# Maket.net
KiCad netlist of a schematic drawn in Altium Designer
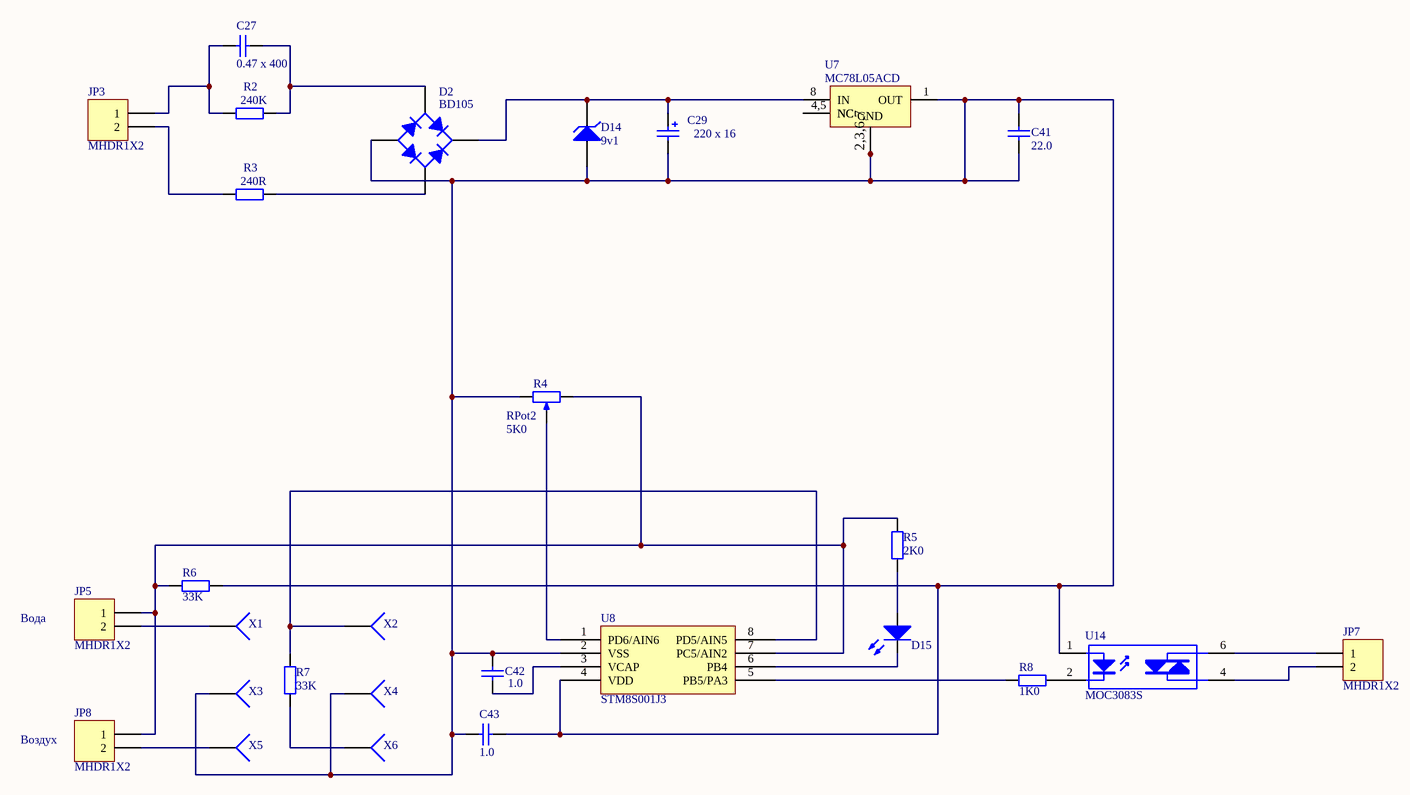
[diagram p0: Maket.SchDoc]

(export (version "E")
  (design (tool "Eeschema 10.0.6"))
  (components
    (comp (ref "C27")
      (value "0.47 x 400")
      (footprint "_1206")
      (description "Capacitor")
      (fields (field (name "MANUFACTURER") "Generic Components") (field (name "PUBLISHER") "Altium Limited"))
      (libsource (lib "Miscellaneous Devices") (part "Cap Semi"))
    )
    (comp (ref "C29")
      (value "220 x 16")
      (footprint "el3")
      (description "Polarized Capacitor (Radial)")
      (fields (field (name "MANUFACTURER") "Generic Components") (field (name "PUBLISHER") "Altium Limited"))
      (libsource (lib "PAL") (part "Cap Pol1"))
    )
    (comp (ref "C41")
      (value "22.0")
      (footprint "_1206")
      (description "Capacitor (Semiconductor SIM Model)")
      (fields (field (name "MANUFACTURER") "Generic Components") (field (name "PUBLISHER") "Altium Limited"))
      (libsource (lib "Miscellaneous Devices") (part "Cap Semi"))
    )
    (comp (ref "C42")
      (value "1.0")
      (footprint "_1206")
      (description "Capacitor")
      (fields (field (name "MANUFACTURER") "Generic Components") (field (name "PUBLISHER") "Altium Limited"))
      (libsource (lib "Miscellaneous Devices") (part "Cap Semi"))
    )
    (comp (ref "C43")
      (value "1.0")
      (footprint "_1206")
      (description "Capacitor")
      (fields (field (name "MANUFACTURER") "Generic Components") (field (name "PUBLISHER") "Altium Limited"))
      (libsource (lib "Miscellaneous Devices") (part "Cap Semi"))
    )
    (comp (ref "D2")
      (value "BD105")
      (footprint "DF01")
      (description "Full Wave Diode Bridge")
      (fields (field (name "MANUFACTURER") "Generic Components") (field (name "PUBLISHER") "Altium Limited"))
      (libsource (lib "Miscellaneous Devices") (part "Bridge1"))
    )
    (comp (ref "D14")
      (value "9v1")
      (footprint "DIODE-0.7")
      (description "Zener Diode")
      (fields (field (name "MANUFACTURER") "Generic Components") (field (name "PUBLISHER") "Altium Limited"))
      (libsource (lib "Miscellaneous Devices") (part "D Zener"))
    )
    (comp (ref "D15")
      (value "LED0")
      (footprint "el3")
      (description "Typical INFRARED GaAs LED")
      (fields (field (name "MANUFACTURER") "Generic Components") (field (name "PUBLISHER") "Altium Limited"))
      (libsource (lib "PAL") (part "LED0"))
    )
    (comp (ref "JP3")
      (value "MHDR1X2")
      (footprint "MHDR1X2")
      (description "Header, 2-Pin")
      (fields (field (name "MANUFACTURER") "Generic Components") (field (name "PUBLISHER") "Altium Limited"))
      (libsource (lib "") (part "MHDR1X2_1"))
    )
    (comp (ref "JP5")
      (value "MHDR1X2")
      (footprint "MHDR1X2")
      (description "Header, 2-Pin")
      (fields (field (name "MANUFACTURER") "Generic Components") (field (name "PUBLISHER") "Altium Limited"))
      (libsource (lib "") (part "MHDR1X2_1"))
    )
    (comp (ref "JP7")
      (value "MHDR1X2")
      (footprint "MHDR1X2")
      (description "Header, 2-Pin")
      (fields (field (name "MANUFACTURER") "Generic Components") (field (name "PUBLISHER") "Altium Limited"))
      (libsource (lib "Miscellaneous Connectors") (part "MHDR1X2"))
    )
    (comp (ref "JP8")
      (value "MHDR1X2")
      (footprint "MHDR1X2")
      (description "Header, 2-Pin")
      (fields (field (name "MANUFACTURER") "Generic Components") (field (name "PUBLISHER") "Altium Limited"))
      (libsource (lib "") (part "MHDR1X2_1"))
    )
    (comp (ref "R2")
      (value "240K")
      (footprint "_1206")
      (description "Resistor")
      (fields (field (name "MANUFACTURER") "Generic Components") (field (name "PUBLISHER") "Altium Limited"))
      (libsource (lib "Miscellaneous Devices") (part "Res2"))
    )
    (comp (ref "R3")
      (value "240R")
      (footprint "_1206")
      (description "Resistor")
      (fields (field (name "MANUFACTURER") "Generic Components") (field (name "PUBLISHER") "Altium Limited"))
      (libsource (lib "Miscellaneous Devices") (part "Res2"))
    )
    (comp (ref "R4")
      (value "RPot2")
      (footprint "VR2")
      (description "Potentiometer")
      (fields
        (field (name "MANUFACTURER") "Generic Components")
        (field (name "ALTIUM_VALUE") "5K0")
        (field (name "PUBLISHER") "Altium Limited")
      )
      (libsource (lib "Miscellaneous Devices") (part "RPot2"))
    )
    (comp (ref "R5")
      (value "2K0")
      (footprint "_1206")
      (description "Resistor")
      (fields (field (name "MANUFACTURER") "Generic Components") (field (name "PUBLISHER") "Altium Limited"))
      (libsource (lib "") (part "Res2_3"))
    )
    (comp (ref "R6")
      (value "33K")
      (footprint "_1206")
      (description "Resistor")
      (fields (field (name "MANUFACTURER") "Generic Components") (field (name "PUBLISHER") "Altium Limited"))
      (libsource (lib "") (part "Res2_2"))
    )
    (comp (ref "R7")
      (value "33K")
      (footprint "_1206")
      (description "Resistor")
      (fields (field (name "MANUFACTURER") "Generic Components") (field (name "PUBLISHER") "Altium Limited"))
      (libsource (lib "Miscellaneous Devices") (part "Res2"))
    )
    (comp (ref "R8")
      (value "1K0")
      (footprint "_1206")
      (description "Resistor")
      (fields (field (name "MANUFACTURER") "Generic Components") (field (name "PUBLISHER") "Altium Limited"))
      (libsource (lib "") (part "Res2_1"))
    )
    (comp (ref "U7")
      (value "MC78L05ACD")
      (footprint "SO-G8")
      (description "3-Terminal Low-Current Positive Fixed Voltage Regulator")
      (fields (field (name "MANUFACTURER") "Motorola") (field (name "PUBLISHER") "Altium Limited"))
      (libsource (lib "PAL") (part "MC78L05ACD"))
    )
    (comp (ref "U8") (value "STM8S001J3") (libsource (lib "PAL") (part "STM8S001J3")))
    (comp (ref "U14")
      (value "MOC3083S")
      (footprint "smdip6")
      (description "Opto-Triac")
      (fields (field (name "MANUFACTURER") "Generic Components") (field (name "PUBLISHER") "Altium Limited"))
      (libsource (lib "PAL") (part "Opto TRIAC"))
    )
    (comp (ref "X1")
      (value "~")
      (footprint "PIN1")
      (description "Socket")
      (fields (field (name "MANUFACTURER") "Generic Components") (field (name "PUBLISHER") "Altium Limited"))
      (libsource (lib "Miscellaneous Connectors") (part "Socket"))
    )
    (comp (ref "X2")
      (value "~")
      (footprint "PIN1")
      (description "Socket")
      (fields (field (name "MANUFACTURER") "Generic Components") (field (name "PUBLISHER") "Altium Limited"))
      (libsource (lib "Miscellaneous Connectors") (part "Socket"))
    )
    (comp (ref "X3")
      (value "~")
      (footprint "PIN1")
      (description "Socket")
      (fields (field (name "MANUFACTURER") "Generic Components") (field (name "PUBLISHER") "Altium Limited"))
      (libsource (lib "Miscellaneous Connectors") (part "Socket"))
    )
    (comp (ref "X4")
      (value "~")
      (footprint "PIN1")
      (description "Socket")
      (fields (field (name "MANUFACTURER") "Generic Components") (field (name "PUBLISHER") "Altium Limited"))
      (libsource (lib "Miscellaneous Connectors") (part "Socket"))
    )
    (comp (ref "X5")
      (value "~")
      (footprint "PIN1")
      (description "Socket")
      (fields (field (name "MANUFACTURER") "Generic Components") (field (name "PUBLISHER") "Altium Limited"))
      (libsource (lib "Miscellaneous Connectors") (part "Socket"))
    )
    (comp (ref "X6")
      (value "~")
      (footprint "PIN1")
      (description "Socket")
      (fields (field (name "MANUFACTURER") "Generic Components") (field (name "PUBLISHER") "Altium Limited"))
      (libsource (lib "Miscellaneous Connectors") (part "Socket"))
    )
  )
  (nets
    (net (code "1") (name "Net-(C27-Pad1)") (class "Default")
      (node (ref "C27") (pin "1") (pinfunction "1_1") (pintype "passive"))
      (node (ref "D2") (pin "2") (pinfunction "C_2") (pintype "passive"))
      (node (ref "R2") (pin "1") (pinfunction "1_1") (pintype "passive"))
    )
    (net (code "2") (name "Net-(C27-Pad2)") (class "Default")
      (node (ref "C27") (pin "2") (pinfunction "2_2") (pintype "passive"))
      (node (ref "JP3") (pin "1") (pinfunction "1_1") (pintype "passive"))
      (node (ref "R2") (pin "2") (pinfunction "2_2") (pintype "passive"))
    )
    (net (code "3") (name "Net-(D2-C-Pad4)") (class "Default")
      (node (ref "D2") (pin "4") (pinfunction "C_4") (pintype "passive"))
      (node (ref "R3") (pin "1") (pinfunction "1_1") (pintype "passive"))
    )
    (net (code "4") (name "Net-(D14-A)") (class "Default")
      (node (ref "C29") (pin "2") (pinfunction "2_2") (pintype "passive"))
      (node (ref "C41") (pin "1") (pinfunction "1_1") (pintype "passive"))
      (node (ref "C41") (pin "2") (pinfunction "2_2") (pintype "passive"))
      (node (ref "C42") (pin "2") (pinfunction "2_2") (pintype "passive"))
      (node (ref "C43") (pin "1") (pinfunction "1_1") (pintype "passive"))
      (node (ref "C43") (pin "2") (pinfunction "2_2") (pintype "passive"))
      (node (ref "D14") (pin "1") (pinfunction "A_1") (pintype "passive"))
      (node (ref "D2") (pin "1") (pinfunction "A_1") (pintype "passive"))
      (node (ref "R4") (pin "1") (pinfunction "TOP_1") (pintype "passive"))
      (node (ref "R6") (pin "2") (pinfunction "2_2") (pintype "passive"))
      (node (ref "U14") (pin "1") (pinfunction "A_1") (pintype "passive"))
      (node (ref "U7") (pin "1") (pinfunction "OUT_1") (pintype "power_in"))
      (node (ref "U7") (pin "2") (pinfunction "GND_2") (pintype "power_in"))
      (node (ref "U7") (pin "3") (pinfunction "GND_3") (pintype "power_in"))
      (node (ref "U7") (pin "6") (pinfunction "GND_6") (pintype "power_in"))
      (node (ref "U7") (pin "7") (pinfunction "GND_7") (pintype "power_in"))
      (node (ref "U8") (pin "2") (pinfunction "VSS_2") (pintype "passive"))
      (node (ref "U8") (pin "4") (pinfunction "VDD_4") (pintype "passive"))
      (node (ref "X3") (pin "1") (pinfunction "1_1") (pintype "passive"))
      (node (ref "X4") (pin "1") (pinfunction "1_1") (pintype "passive"))
    )
    (net (code "5") (name "Net-(D14-K)") (class "Default")
      (node (ref "C29") (pin "1") (pinfunction "1_1") (pintype "passive"))
      (node (ref "D14") (pin "2") (pinfunction "K_2") (pintype "passive"))
      (node (ref "D2") (pin "3") (pinfunction "K_3") (pintype "passive"))
      (node (ref "U7") (pin "8") (pinfunction "IN_8") (pintype "power_in"))
    )
    (net (code "6") (name "Net-(D15-A)") (class "Default")
      (node (ref "D15") (pin "1") (pinfunction "A_1") (pintype "passive"))
      (node (ref "R5") (pin "1") (pinfunction "1_1") (pintype "passive"))
    )
    (net (code "7") (name "Net-(D15-K)") (class "Default")
      (node (ref "D15") (pin "2") (pinfunction "K_2") (pintype "passive"))
      (node (ref "U8") (pin "6") (pinfunction "PB4_6") (pintype "passive"))
    )
    (net (code "8") (name "Net-(JP3-Pad2)") (class "Default")
      (node (ref "JP3") (pin "2") (pinfunction "2_2") (pintype "passive"))
      (node (ref "R3") (pin "2") (pinfunction "2_2") (pintype "passive"))
    )
    (net (code "9") (name "Net-(JP5-Pad2)") (class "Default")
      (node (ref "JP5") (pin "2") (pinfunction "2_2") (pintype "passive"))
      (node (ref "X1") (pin "1") (pinfunction "1_1") (pintype "passive"))
    )
    (net (code "10") (name "Net-(JP7-Pad1)") (class "Default")
      (node (ref "JP7") (pin "1") (pinfunction "1_1") (pintype "passive"))
      (node (ref "U14") (pin "6") (pinfunction "A/K_6") (pintype "passive"))
    )
    (net (code "11") (name "Net-(JP7-Pad2)") (class "Default")
      (node (ref "JP7") (pin "2") (pinfunction "2_2") (pintype "passive"))
      (node (ref "U14") (pin "4") (pinfunction "A/K_4") (pintype "passive"))
    )
    (net (code "12") (name "Net-(JP8-Pad2)") (class "Default")
      (node (ref "JP8") (pin "2") (pinfunction "2_2") (pintype "passive"))
      (node (ref "X5") (pin "1") (pinfunction "1_1") (pintype "passive"))
    )
    (net (code "13") (name "Net-(R4-BOT)") (class "Default")
      (node (ref "JP5") (pin "1") (pinfunction "1_1") (pintype "passive"))
      (node (ref "JP8") (pin "1") (pinfunction "1_1") (pintype "passive"))
      (node (ref "R4") (pin "2") (pinfunction "BOT_2") (pintype "passive"))
      (node (ref "R5") (pin "2") (pinfunction "2_2") (pintype "passive"))
      (node (ref "R6") (pin "1") (pinfunction "1_1") (pintype "passive"))
      (node (ref "U8") (pin "7") (pinfunction "PC5/AIN2_7") (pintype "passive"))
    )
    (net (code "14") (name "Net-(R4-TAP)") (class "Default")
      (node (ref "R4") (pin "3") (pinfunction "TAP_3") (pintype "passive"))
      (node (ref "U8") (pin "1") (pinfunction "PD6/AIN6_1") (pintype "passive"))
    )
    (net (code "15") (name "Net-(R7-Pad2)") (class "Default")
      (node (ref "R7") (pin "2") (pinfunction "2_2") (pintype "passive"))
      (node (ref "X6") (pin "1") (pinfunction "1_1") (pintype "passive"))
    )
    (net (code "16") (name "Net-(U7-NC-Pad4)") (class "Default")
      (node (ref "U7") (pin "4") (pinfunction "NC_4") (pintype "passive"))
      (node (ref "U7") (pin "5") (pinfunction "NC_5") (pintype "passive"))
    )
    (net (code "17") (name "Net-(U8-PB5{slash}PA3)") (class "Default")
      (node (ref "R8") (pin "2") (pinfunction "2_2") (pintype "passive"))
      (node (ref "U8") (pin "5") (pinfunction "PB5/PA3_5") (pintype "passive"))
    )
    (net (code "18") (name "Net-(U8-PD5{slash}AIN5)") (class "Default")
      (node (ref "R7") (pin "1") (pinfunction "1_1") (pintype "passive"))
      (node (ref "U8") (pin "8") (pinfunction "PD5/AIN5_8") (pintype "passive"))
      (node (ref "X2") (pin "1") (pinfunction "1_1") (pintype "passive"))
    )
    (net (code "19") (name "Net-(U8-VCAP)") (class "Default")
      (node (ref "C42") (pin "1") (pinfunction "1_1") (pintype "passive"))
      (node (ref "U8") (pin "3") (pinfunction "VCAP_3") (pintype "passive"))
    )
    (net (code "20") (name "Net-(U14-K)") (class "Default")
      (node (ref "R8") (pin "1") (pinfunction "1_1") (pintype "passive"))
      (node (ref "U14") (pin "2") (pinfunction "K_2") (pintype "passive"))
    )
  )
)
